# ControllerSupplySwitch.net
KiCad netlist of a schematic drawn in Altium Designer
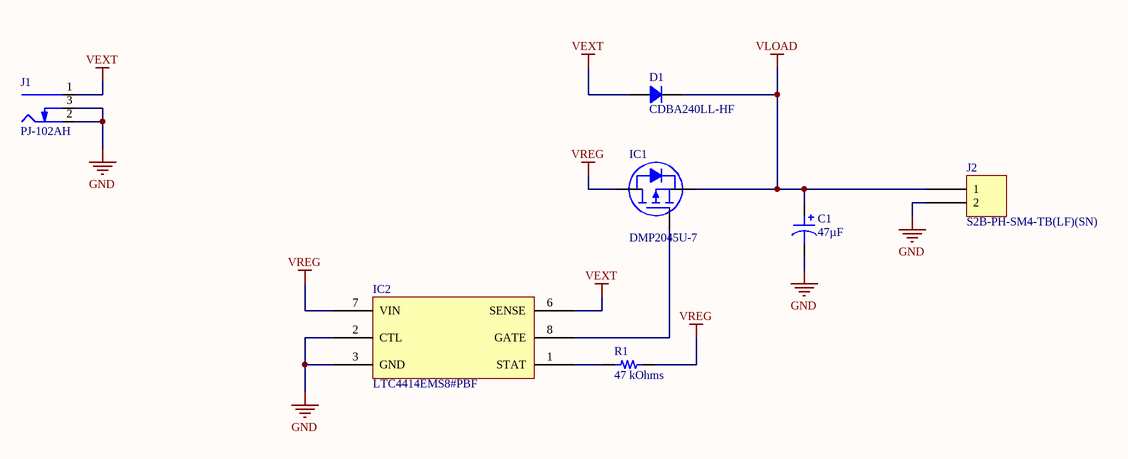
[diagram p0: ControllerSupplySwitch.SchDoc]

(export (version "E")
  (design (tool "Eeschema 10.0.6"))
  (components
    (comp (ref "C1")
      (value "47µF")
      (footprint "CAP ALSMD 6.6MM H6.1MM")
      (description "ALUMINUM CAPACITOR")
      (fields
        (field (name "PART NUMBER") "HHXD250ARA470MF61G")
        (field (name "MANUFACTURER") "United Chemi-Con")
      )
      (libsource (lib "Celestial Altium Library - altium_library") (part "Polarised Capacitor"))
    )
    (comp (ref "D1")
      (value "CDBA240LL-HF")
      (footprint "DO214AC SMA")
      (description "DIODE SCHOTTKY 40V 2A DO214AC")
      (fields (field (name "MANUFACTURER") "Comchip Technology"))
      (libsource (lib "Celestial Altium Library - altium_library") (part "Diode"))
    )
    (comp (ref "IC1")
      (value "DMP2045U-7")
      (footprint "DIODES SOT-23-3")
      (description "MOSFET P-CHAN 24V SOT23")
      (fields (field (name "MANUFACTURER") "Diodes Incorporated"))
      (libsource (lib "Celestial Altium Library - altium_library") (part "DIODES MOSFET P-CH SOT-23-3"))
    )
    (comp (ref "IC2")
      (value "LTC4414EMS8#PBF")
      (footprint "ANALOG MSOP-8 RM-8")
      (description "IC OR CTRLR SRC SELECT 8MSOP")
      (fields (field (name "MANUFACTURER") "Linear Technology/Analog Devices"))
      (libsource (lib "Celestial Altium Library - altium_library") (part "ANALOG LTC4414"))
    )
    (comp (ref "J1")
      (value "PJ-102AH")
      (footprint "CUI PJ-102AH")
      (description "CONN PWR JACK 2X5.5MM SOLDER")
      (fields (field (name "MANUFACTURER") "CUI Devices"))
      (libsource (lib "Celestial Altium Library - altium_library") (part "Barrel Connector"))
    )
    (comp (ref "J2")
      (value "S2B-PH-SM4-TB(LF)(SN)")
      (footprint "JST S2B-PH-SM4-TB")
      (description "CONN HEADER SMD R/A 2POS 2MM")
      (fields (field (name "MANUFACTURER") "JST Sales America Inc."))
      (libsource (lib "Celestial Altium Library - altium_library") (part "2 Pin"))
    )
    (comp (ref "R1")
      (value "47 kOhms")
      (footprint "RES 0603_1608")
      (description "RES SMD 47K OHM 5% 1/4W 0603")
      (fields
        (field (name "PART NUMBER") "ERJ-PA3J473V")
        (field (name "MANUFACTURER") "Panasonic Electronic Components")
      )
      (libsource (lib "Celestial Altium Library - altium_library") (part "Resistor"))
    )
  )
  (nets
    (net (code "1") (name "GND") (class "Default")
      (node (ref "C1") (pin "2") (pinfunction "2_2") (pintype "passive"))
      (node (ref "IC2") (pin "2") (pinfunction "CTL_2") (pintype "passive"))
      (node (ref "IC2") (pin "3") (pinfunction "GND_3") (pintype "passive"))
      (node (ref "J1") (pin "2") (pinfunction "Outer_2") (pintype "passive"))
      (node (ref "J1") (pin "3") (pinfunction "SW_3") (pintype "passive"))
      (node (ref "J2") (pin "2") (pinfunction "2_2") (pintype "passive"))
    )
    (net (code "2") (name "Net-(IC1-G)") (class "Default")
      (node (ref "IC1") (pin "1") (pinfunction "G_1") (pintype "passive"))
      (node (ref "IC2") (pin "8") (pinfunction "GATE_8") (pintype "passive"))
    )
    (net (code "3") (name "Net-(IC2-STAT)") (class "Default")
      (node (ref "IC2") (pin "1") (pinfunction "STAT_1") (pintype "passive"))
      (node (ref "R1") (pin "1") (pinfunction "1_1") (pintype "passive"))
    )
    (net (code "4") (name "VEXT") (class "Default")
      (node (ref "D1") (pin "1") (pinfunction "1_1") (pintype "passive"))
      (node (ref "IC2") (pin "6") (pinfunction "SENSE_6") (pintype "passive"))
      (node (ref "J1") (pin "1") (pinfunction "Centre_1") (pintype "passive"))
    )
    (net (code "5") (name "VLOAD") (class "Default")
      (node (ref "C1") (pin "1") (pinfunction "1_1") (pintype "passive"))
      (node (ref "D1") (pin "2") (pinfunction "2_2") (pintype "passive"))
      (node (ref "IC1") (pin "2") (pinfunction "S_2") (pintype "passive"))
      (node (ref "J2") (pin "1") (pinfunction "1_1") (pintype "passive"))
    )
    (net (code "6") (name "VREG") (class "Default")
      (node (ref "IC1") (pin "3") (pinfunction "D_3") (pintype "passive"))
      (node (ref "IC2") (pin "7") (pinfunction "VIN_7") (pintype "passive"))
      (node (ref "R1") (pin "2") (pinfunction "2_2") (pintype "passive"))
    )
  )
)
